# Lilypad_Power_Supply.net
KiCad netlist of a schematic drawn in EAGLE
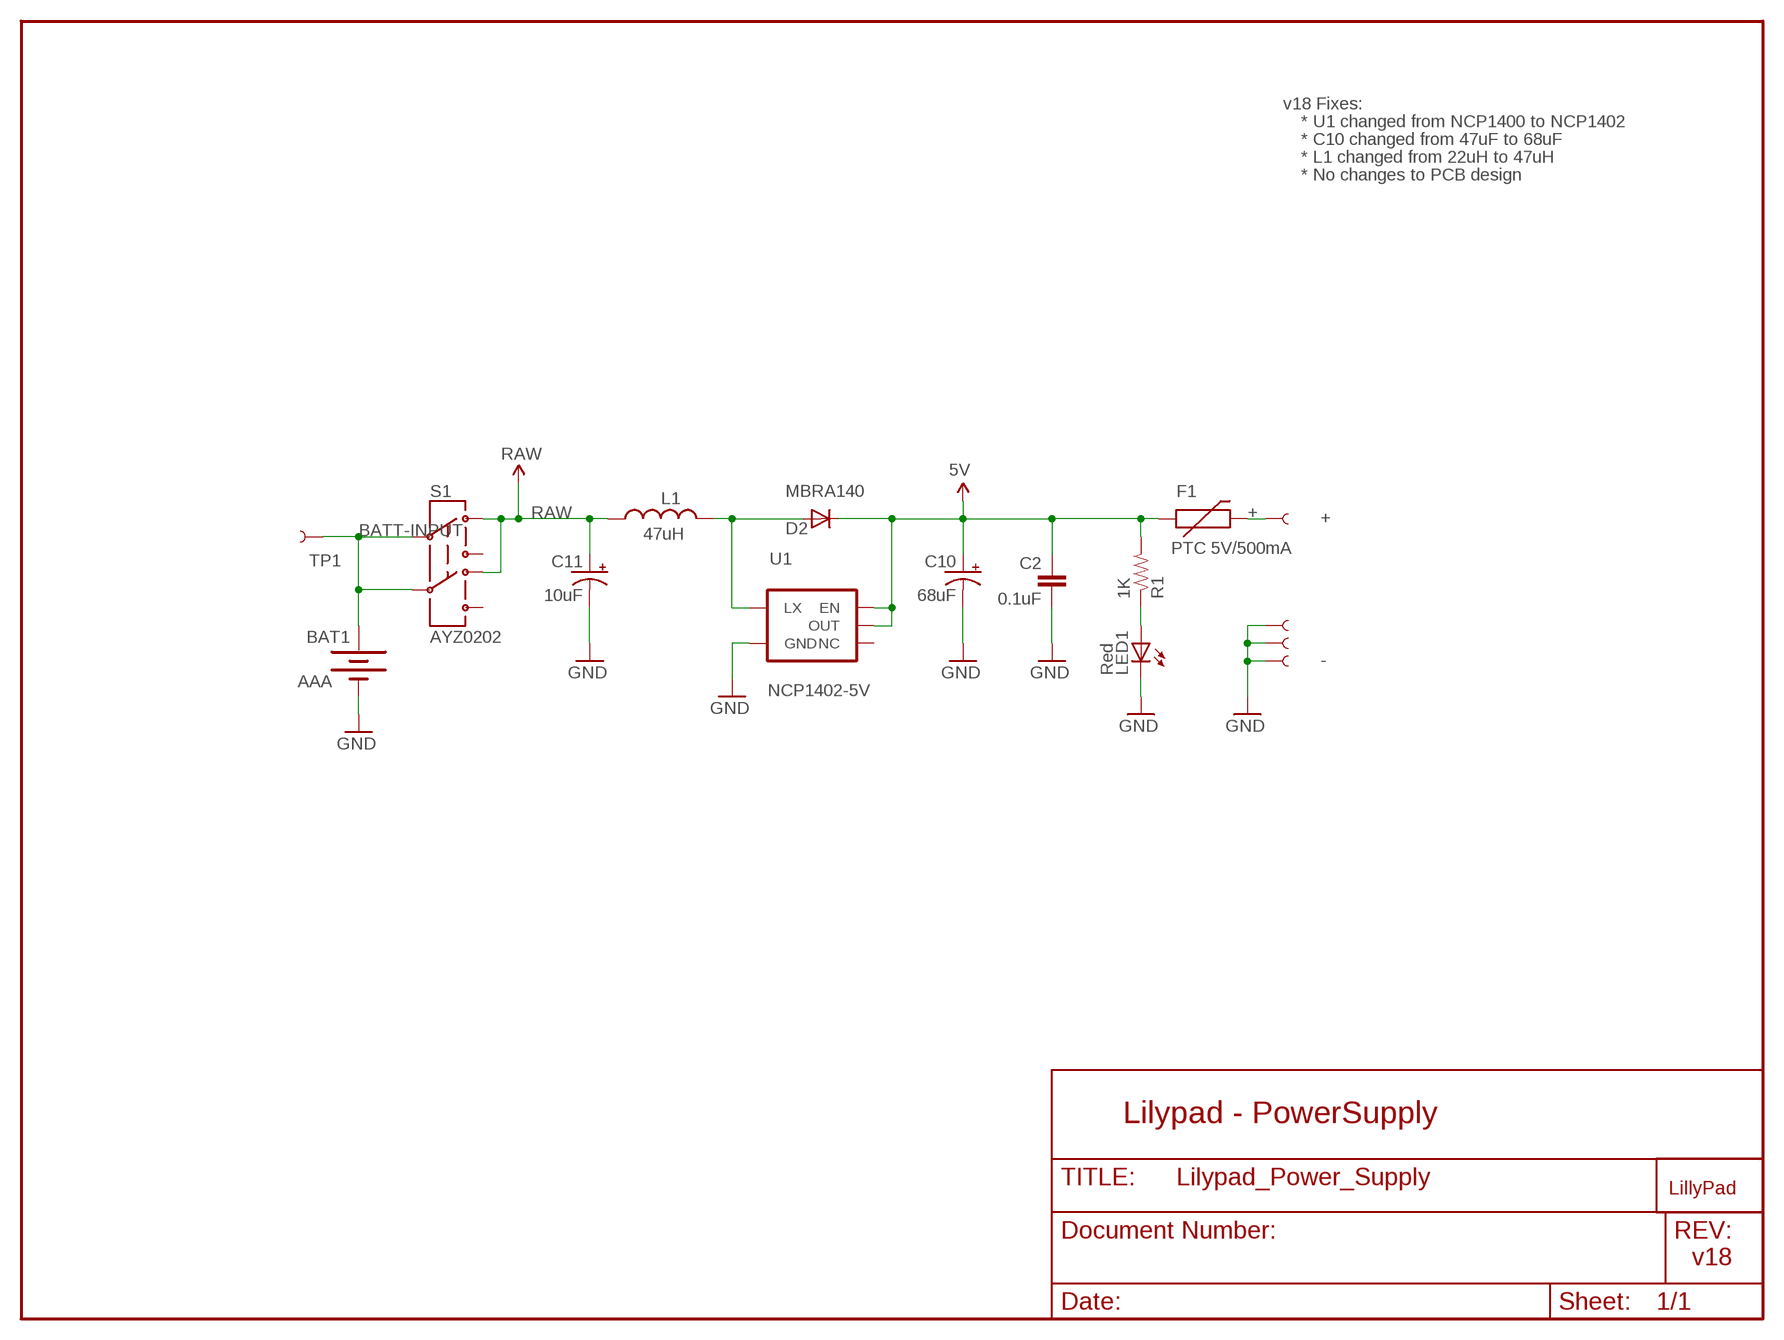
[diagram p0: schematic, sheet 1]

(export (version "E")
  (design (tool "Eeschema 10.0.6"))
  (components
    (comp (ref "BAT1")
      (value "AAA")
      (footprint "eagle-import:BATTERY-AAA")
      (libsource (lib "eagle-import") (part "BATTERYAAA"))
    )
    (comp (ref "C2")
      (value "0.1uF")
      (footprint "eagle-import:0603-CAP")
      (libsource (lib "eagle-import") (part "CAP0603-CAP"))
    )
    (comp (ref "C10")
      (value "68uF")
      (footprint "eagle-import:EIA3528-21")
      (libsource (lib "eagle-import") (part "CAP_POL2"))
    )
    (comp (ref "C11")
      (value "10uF")
      (footprint "eagle-import:CPOL_1206")
      (libsource (lib "eagle-import") (part "CAP_POL1206"))
    )
    (comp (ref "D2")
      (value "MBRA140")
      (footprint "eagle-import:SMA-DIODE")
      (libsource (lib "eagle-import") (part "DIODESMA"))
    )
    (comp (ref "F1")
      (value "PTC 5V/500mA")
      (footprint "eagle-import:PTC-1206")
      (libsource (lib "eagle-import") (part "PTCSMD"))
    )
    (comp (ref "L1")
      (value "47uH")
      (footprint "eagle-import:CR54")
      (libsource (lib "eagle-import") (part "INDUCTORCR54"))
    )
    (comp (ref "LED1")
      (value "Red")
      (footprint "eagle-import:LED-1206")
      (libsource (lib "eagle-import") (part "LED1206"))
    )
    (comp (ref "R1")
      (value "1K")
      (footprint "eagle-import:0603-RES")
      (libsource (lib "eagle-import") (part "RESISTOR0603-RES"))
    )
    (comp (ref "S1")
      (value "AYZ0202")
      (footprint "eagle-import:AYZ0202")
      (libsource (lib "eagle-import") (part "AYZ0202"))
    )
    (comp (ref "TP1")
      (value "TEST-POINT3X5")
      (footprint "eagle-import:PAD.03X.05")
      (libsource (lib "eagle-import") (part "TEST-POINT3X5"))
    )
    (comp (ref "U$1")
      (value "SEWTAP10")
      (footprint "eagle-import:PETAL-LONG-2-2SIDE")
      (libsource (lib "eagle-import") (part "SEWTAP10"))
    )
    (comp (ref "U$2")
      (value "SEWTAP10")
      (footprint "eagle-import:PETAL-LONG-2-2SIDE")
      (libsource (lib "eagle-import") (part "SEWTAP10"))
    )
    (comp (ref "U$4")
      (value "SEWTAP10")
      (footprint "eagle-import:PETAL-LONG-2-2SIDE")
      (libsource (lib "eagle-import") (part "SEWTAP10"))
    )
    (comp (ref "U$5")
      (value "SEWTAP10")
      (footprint "eagle-import:PETAL-LONG-2-2SIDE")
      (libsource (lib "eagle-import") (part "SEWTAP10"))
    )
    (comp (ref "U$7")
      (value "LOGO-LPLP")
      (footprint "eagle-import:LOGO-LILYPAD")
      (libsource (lib "eagle-import") (part "LOGO-LPLP"))
    )
    (comp (ref "U1")
      (value "NCP1402-5V")
      (footprint "eagle-import:SOT23-5")
      (libsource (lib "eagle-import") (part "V_REG_NCP1400SOT23-5"))
    )
  )
  (nets
    (net (code "1") (name "/+") (class "Default")
      (node (ref "F1") (pin "2") (pinfunction "2_2") (pintype "bidirectional"))
      (node (ref "U$1") (pin "1") (pinfunction "1_1") (pintype "bidirectional"))
    )
    (net (code "2") (name "/BATT-INPUT") (class "Default")
      (node (ref "BAT1") (pin "PWR@1") (pinfunction "+_PWR@1") (pintype "power_in"))
      (node (ref "S1") (pin "2") (pinfunction "2_2") (pintype "bidirectional"))
      (node (ref "S1") (pin "5") (pinfunction "5_5") (pintype "bidirectional"))
      (node (ref "TP1") (pin "P$1") (pinfunction "1_P$1") (pintype "bidirectional"))
    )
    (net (code "3") (name "5V") (class "Default")
      (node (ref "C10") (pin "A") (pinfunction "+_A") (pintype "passive"))
      (node (ref "C2") (pin "1") (pinfunction "1_1") (pintype "passive"))
      (node (ref "D2") (pin "C") (pinfunction "C_C") (pintype "passive"))
      (node (ref "F1") (pin "1") (pinfunction "1_1") (pintype "bidirectional"))
      (node (ref "R1") (pin "2") (pinfunction "2_2") (pintype "passive"))
      (node (ref "U1") (pin "1") (pinfunction "EN_1") (pintype "input"))
      (node (ref "U1") (pin "2") (pinfunction "OUT_2") (pintype "passive"))
    )
    (net (code "4") (name "GND") (class "Default")
      (node (ref "BAT1") (pin "GND@1") (pinfunction "-_GND@1") (pintype "power_in"))
      (node (ref "C10") (pin "C") (pinfunction "-_C") (pintype "passive"))
      (node (ref "C11") (pin "C") (pinfunction "-_C") (pintype "passive"))
      (node (ref "C2") (pin "2") (pinfunction "2_2") (pintype "passive"))
      (node (ref "LED1") (pin "C") (pinfunction "C_C") (pintype "passive"))
      (node (ref "U$2") (pin "1") (pinfunction "1_1") (pintype "bidirectional"))
      (node (ref "U$4") (pin "1") (pinfunction "1_1") (pintype "bidirectional"))
      (node (ref "U$5") (pin "1") (pinfunction "1_1") (pintype "bidirectional"))
      (node (ref "U1") (pin "4") (pinfunction "GND_4") (pintype "input"))
    )
    (net (code "5") (name "Net-(L1-1)") (class "Default")
      (node (ref "D2") (pin "A") (pinfunction "A_A") (pintype "passive"))
      (node (ref "L1") (pin "P$1") (pinfunction "1_P$1") (pintype "passive"))
      (node (ref "U1") (pin "5") (pinfunction "LX_5") (pintype "input"))
    )
    (net (code "6") (name "Net-(LED1-PadA)") (class "Default")
      (node (ref "LED1") (pin "A") (pinfunction "A_A") (pintype "passive"))
      (node (ref "R1") (pin "1") (pinfunction "1_1") (pintype "passive"))
    )
    (net (code "7") (name "RAW") (class "Default")
      (node (ref "C11") (pin "A") (pinfunction "+_A") (pintype "passive"))
      (node (ref "L1") (pin "P$2") (pinfunction "2_P$2") (pintype "passive"))
      (node (ref "S1") (pin "3") (pinfunction "1_3") (pintype "bidirectional"))
      (node (ref "S1") (pin "6") (pinfunction "4_6") (pintype "bidirectional"))
    )
    (net (code "8") (name "unconnected-(S1-3-Pad1)") (class "Default")
      (node (ref "S1") (pin "1") (pinfunction "3_1") (pintype "bidirectional"))
    )
    (net (code "9") (name "unconnected-(S1-6-Pad4)") (class "Default")
      (node (ref "S1") (pin "4") (pinfunction "6_4") (pintype "bidirectional"))
    )
    (net (code "10") (name "unconnected-(U1-NC-Pad3)") (class "Default")
      (node (ref "U1") (pin "3") (pinfunction "NC_3") (pintype "input"))
    )
  )
)
